# 7segement4digits1badidea-max7219-smd-mk-.net
KiCad netlist of a schematic drawn in EAGLE
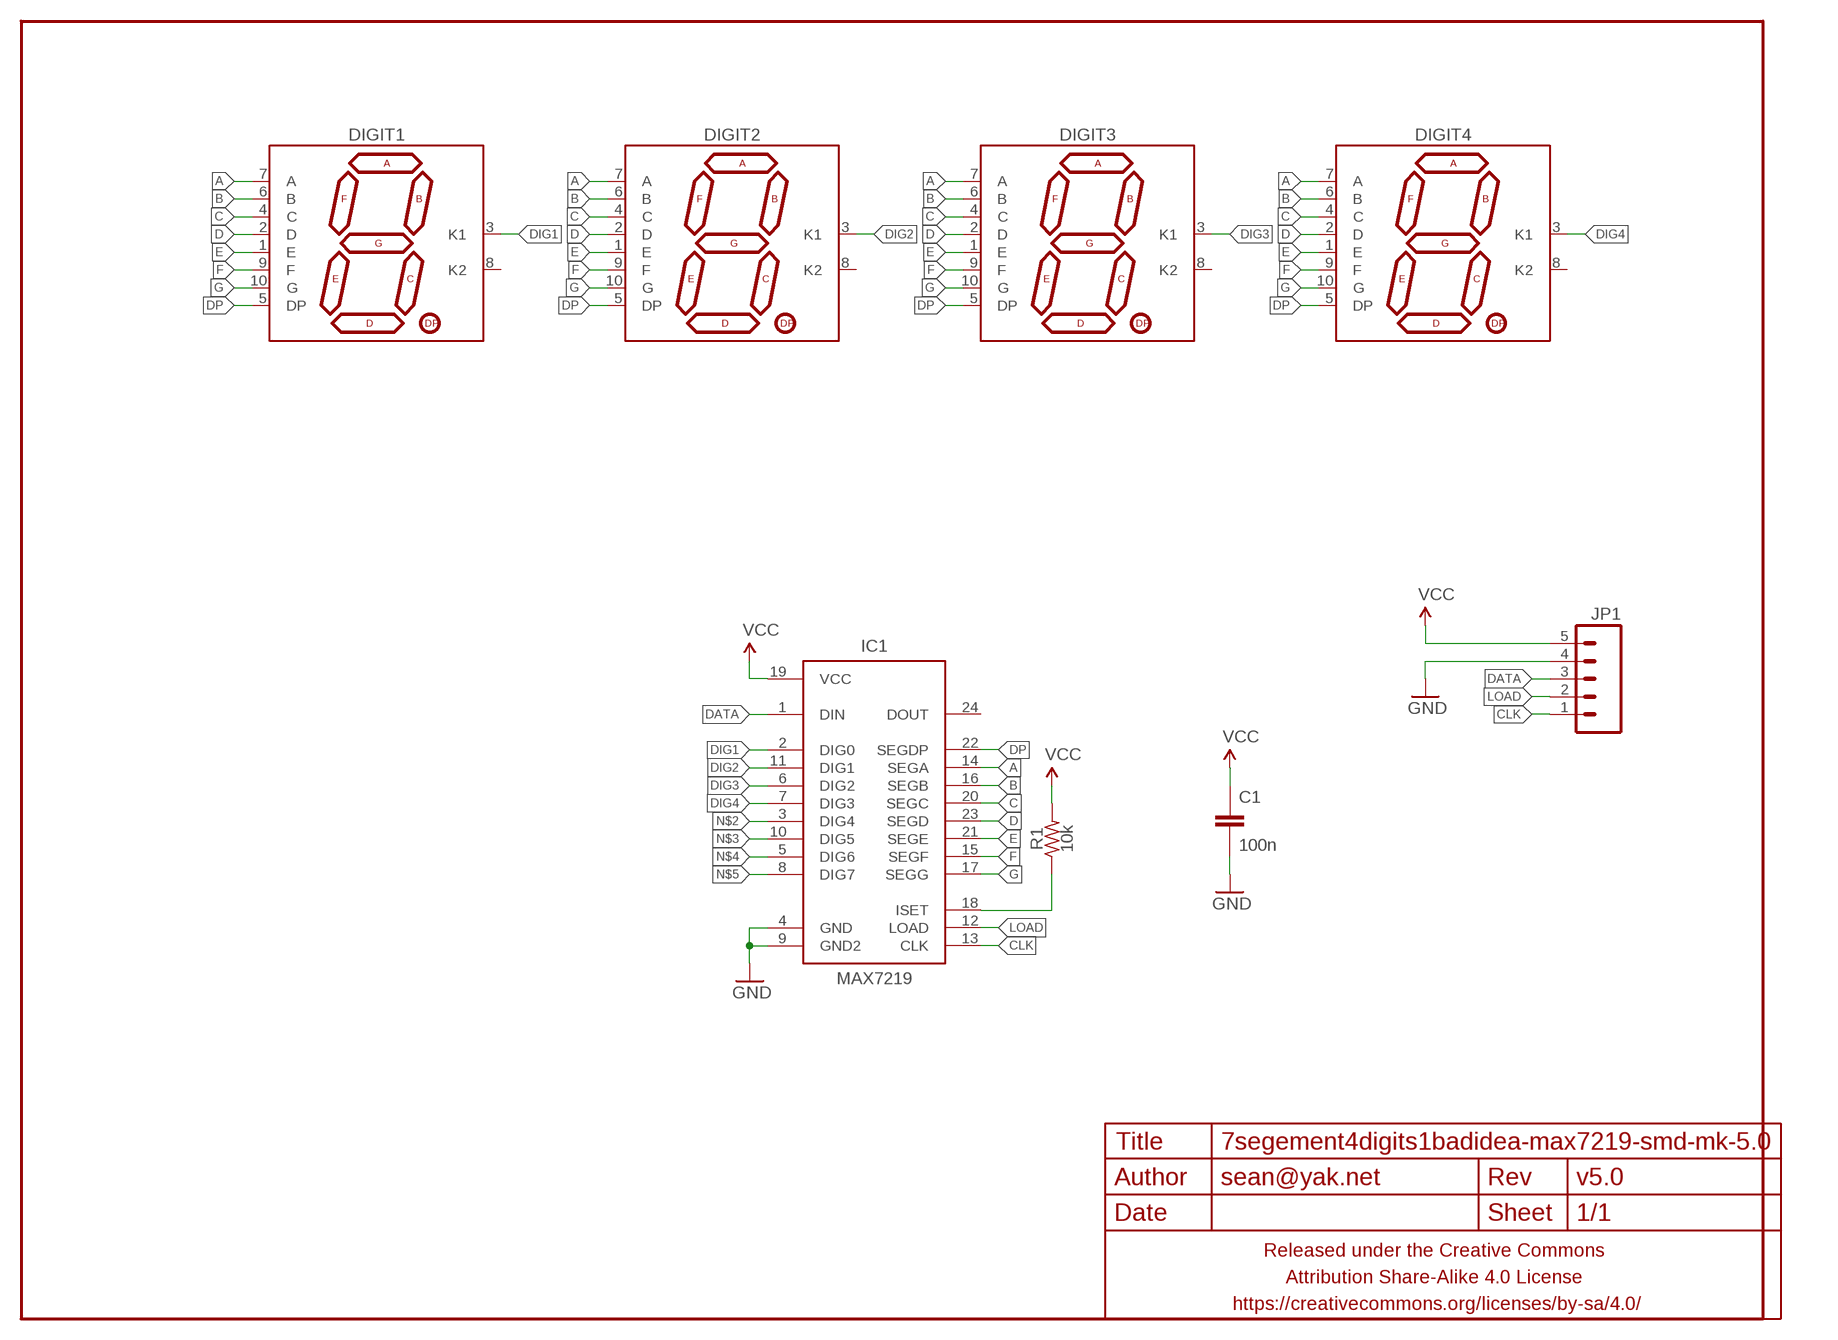
[diagram p0: schematic, sheet 1]

(export (version "E")
  (design (tool "Eeschema 10.0.6"))
  (components
    (comp (ref "C1")
      (value "100n")
      (footprint "eagle-import:C0805")
      (libsource (lib "eagle-import") (part "CAPACITOR-CERAMICC0805"))
    )
    (comp (ref "DIGIT1")
      (value "7SEG_1DIGPTH-25.4MM")
      (footprint "eagle-import:7SEG_1DIG_25.4MM")
      (libsource (lib "eagle-import") (part "7SEG_1DIGPTH-25.4MM"))
    )
    (comp (ref "DIGIT2")
      (value "7SEG_1DIGPTH-25.4MM")
      (footprint "eagle-import:7SEG_1DIG_25.4MM")
      (libsource (lib "eagle-import") (part "7SEG_1DIGPTH-25.4MM"))
    )
    (comp (ref "DIGIT3")
      (value "7SEG_1DIGPTH-25.4MM")
      (footprint "eagle-import:7SEG_1DIG_25.4MM")
      (libsource (lib "eagle-import") (part "7SEG_1DIGPTH-25.4MM"))
    )
    (comp (ref "DIGIT4")
      (value "7SEG_1DIGPTH-25.4MM")
      (footprint "eagle-import:7SEG_1DIG_25.4MM")
      (libsource (lib "eagle-import") (part "7SEG_1DIGPTH-25.4MM"))
    )
    (comp (ref "FRAME1")
      (value "FRAME-LETTERNO_PACKAGE")
      (footprint "eagle-import:DUMMY")
      (fields (field (name "DESIGNER") "sean@yak.net") (field (name "VERSION") "v5.0"))
      (libsource (lib "eagle-import") (part "FRAME-LETTERNO_PACKAGE"))
    )
    (comp (ref "IC1")
      (value "MAX7219")
      (footprint "eagle-import:SO24W")
      (libsource (lib "eagle-import") (part "MAX7219SOIC-W"))
    )
    (comp (ref "JP1")
      (value "M05PTH-CENTERED")
      (footprint "eagle-import:1X05_PTH_CENTERED")
      (libsource (lib "eagle-import") (part "M05PTH-CENTERED"))
    )
    (comp (ref "R1")
      (value "10k")
      (footprint "eagle-import:R0805")
      (libsource (lib "eagle-import") (part "RESISTORR0805"))
    )
  )
  (nets
    (net (code "1") (name "A") (class "Default")
      (node (ref "DIGIT1") (pin "7") (pinfunction "A_7") (pintype "bidirectional"))
      (node (ref "DIGIT2") (pin "7") (pinfunction "A_7") (pintype "bidirectional"))
      (node (ref "DIGIT3") (pin "7") (pinfunction "A_7") (pintype "bidirectional"))
      (node (ref "DIGIT4") (pin "7") (pinfunction "A_7") (pintype "bidirectional"))
      (node (ref "IC1") (pin "14") (pinfunction "SEGA_14") (pintype "bidirectional"))
    )
    (net (code "2") (name "B") (class "Default")
      (node (ref "DIGIT1") (pin "6") (pinfunction "B_6") (pintype "bidirectional"))
      (node (ref "DIGIT2") (pin "6") (pinfunction "B_6") (pintype "bidirectional"))
      (node (ref "DIGIT3") (pin "6") (pinfunction "B_6") (pintype "bidirectional"))
      (node (ref "DIGIT4") (pin "6") (pinfunction "B_6") (pintype "bidirectional"))
      (node (ref "IC1") (pin "16") (pinfunction "SEGB_16") (pintype "bidirectional"))
    )
    (net (code "3") (name "C") (class "Default")
      (node (ref "DIGIT1") (pin "4") (pinfunction "C_4") (pintype "bidirectional"))
      (node (ref "DIGIT2") (pin "4") (pinfunction "C_4") (pintype "bidirectional"))
      (node (ref "DIGIT3") (pin "4") (pinfunction "C_4") (pintype "bidirectional"))
      (node (ref "DIGIT4") (pin "4") (pinfunction "C_4") (pintype "bidirectional"))
      (node (ref "IC1") (pin "20") (pinfunction "SEGC_20") (pintype "bidirectional"))
    )
    (net (code "4") (name "CLK") (class "Default")
      (node (ref "IC1") (pin "13") (pinfunction "CLK_13") (pintype "bidirectional"))
      (node (ref "JP1") (pin "1") (pinfunction "1_1") (pintype "passive"))
    )
    (net (code "5") (name "D") (class "Default")
      (node (ref "DIGIT1") (pin "2") (pinfunction "D_2") (pintype "bidirectional"))
      (node (ref "DIGIT2") (pin "2") (pinfunction "D_2") (pintype "bidirectional"))
      (node (ref "DIGIT3") (pin "2") (pinfunction "D_2") (pintype "bidirectional"))
      (node (ref "DIGIT4") (pin "2") (pinfunction "D_2") (pintype "bidirectional"))
      (node (ref "IC1") (pin "23") (pinfunction "SEGD_23") (pintype "bidirectional"))
    )
    (net (code "6") (name "DATA") (class "Default")
      (node (ref "IC1") (pin "1") (pinfunction "DIN_1") (pintype "bidirectional"))
      (node (ref "JP1") (pin "3") (pinfunction "3_3") (pintype "passive"))
    )
    (net (code "7") (name "DIG1") (class "Default")
      (node (ref "DIGIT1") (pin "3") (pinfunction "K1_3") (pintype "bidirectional"))
      (node (ref "IC1") (pin "2") (pinfunction "DIG0_2") (pintype "bidirectional"))
    )
    (net (code "8") (name "DIG2") (class "Default")
      (node (ref "DIGIT2") (pin "3") (pinfunction "K1_3") (pintype "bidirectional"))
      (node (ref "IC1") (pin "11") (pinfunction "DIG1_11") (pintype "bidirectional"))
    )
    (net (code "9") (name "DIG3") (class "Default")
      (node (ref "DIGIT3") (pin "3") (pinfunction "K1_3") (pintype "bidirectional"))
      (node (ref "IC1") (pin "6") (pinfunction "DIG2_6") (pintype "bidirectional"))
    )
    (net (code "10") (name "DIG4") (class "Default")
      (node (ref "DIGIT4") (pin "3") (pinfunction "K1_3") (pintype "bidirectional"))
      (node (ref "IC1") (pin "7") (pinfunction "DIG3_7") (pintype "bidirectional"))
    )
    (net (code "11") (name "DP") (class "Default")
      (node (ref "DIGIT1") (pin "5") (pinfunction "DP_5") (pintype "bidirectional"))
      (node (ref "DIGIT2") (pin "5") (pinfunction "DP_5") (pintype "bidirectional"))
      (node (ref "DIGIT3") (pin "5") (pinfunction "DP_5") (pintype "bidirectional"))
      (node (ref "DIGIT4") (pin "5") (pinfunction "DP_5") (pintype "bidirectional"))
      (node (ref "IC1") (pin "22") (pinfunction "SEGDP_22") (pintype "bidirectional"))
    )
    (net (code "12") (name "E") (class "Default")
      (node (ref "DIGIT1") (pin "1") (pinfunction "E_1") (pintype "bidirectional"))
      (node (ref "DIGIT2") (pin "1") (pinfunction "E_1") (pintype "bidirectional"))
      (node (ref "DIGIT3") (pin "1") (pinfunction "E_1") (pintype "bidirectional"))
      (node (ref "DIGIT4") (pin "1") (pinfunction "E_1") (pintype "bidirectional"))
      (node (ref "IC1") (pin "21") (pinfunction "SEGE_21") (pintype "bidirectional"))
    )
    (net (code "13") (name "F") (class "Default")
      (node (ref "DIGIT1") (pin "9") (pinfunction "F_9") (pintype "bidirectional"))
      (node (ref "DIGIT2") (pin "9") (pinfunction "F_9") (pintype "bidirectional"))
      (node (ref "DIGIT3") (pin "9") (pinfunction "F_9") (pintype "bidirectional"))
      (node (ref "DIGIT4") (pin "9") (pinfunction "F_9") (pintype "bidirectional"))
      (node (ref "IC1") (pin "15") (pinfunction "SEGF_15") (pintype "bidirectional"))
    )
    (net (code "14") (name "G") (class "Default")
      (node (ref "DIGIT1") (pin "10") (pinfunction "G_10") (pintype "bidirectional"))
      (node (ref "DIGIT2") (pin "10") (pinfunction "G_10") (pintype "bidirectional"))
      (node (ref "DIGIT3") (pin "10") (pinfunction "G_10") (pintype "bidirectional"))
      (node (ref "DIGIT4") (pin "10") (pinfunction "G_10") (pintype "bidirectional"))
      (node (ref "IC1") (pin "17") (pinfunction "SEGG_17") (pintype "bidirectional"))
    )
    (net (code "15") (name "GND") (class "Default")
      (node (ref "C1") (pin "2") (pinfunction "2_2") (pintype "passive"))
      (node (ref "IC1") (pin "4") (pinfunction "GND_4") (pintype "bidirectional"))
      (node (ref "IC1") (pin "9") (pinfunction "GND2_9") (pintype "bidirectional"))
      (node (ref "JP1") (pin "4") (pinfunction "4_4") (pintype "passive"))
    )
    (net (code "16") (name "LOAD") (class "Default")
      (node (ref "IC1") (pin "12") (pinfunction "LOAD_12") (pintype "bidirectional"))
      (node (ref "JP1") (pin "2") (pinfunction "2_2") (pintype "passive"))
    )
    (net (code "17") (name "N$2") (class "Default")
      (node (ref "IC1") (pin "3") (pinfunction "DIG4_3") (pintype "bidirectional"))
    )
    (net (code "18") (name "N$3") (class "Default")
      (node (ref "IC1") (pin "10") (pinfunction "DIG5_10") (pintype "bidirectional"))
    )
    (net (code "19") (name "N$4") (class "Default")
      (node (ref "IC1") (pin "5") (pinfunction "DIG6_5") (pintype "bidirectional"))
    )
    (net (code "20") (name "N$5") (class "Default")
      (node (ref "IC1") (pin "8") (pinfunction "DIG7_8") (pintype "bidirectional"))
    )
    (net (code "21") (name "Net-(IC1-ISET)") (class "Default")
      (node (ref "IC1") (pin "18") (pinfunction "ISET_18") (pintype "bidirectional"))
      (node (ref "R1") (pin "1") (pinfunction "1_1") (pintype "passive"))
    )
    (net (code "22") (name "VCC") (class "Default")
      (node (ref "C1") (pin "1") (pinfunction "1_1") (pintype "passive"))
      (node (ref "IC1") (pin "19") (pinfunction "VCC_19") (pintype "bidirectional"))
      (node (ref "JP1") (pin "5") (pinfunction "5_5") (pintype "passive"))
      (node (ref "R1") (pin "2") (pinfunction "2_2") (pintype "passive"))
    )
    (net (code "23") (name "unconnected-(DIGIT1-K2-Pad8)") (class "Default")
      (node (ref "DIGIT1") (pin "8") (pinfunction "K2_8") (pintype "bidirectional"))
    )
    (net (code "24") (name "unconnected-(DIGIT2-K2-Pad8)") (class "Default")
      (node (ref "DIGIT2") (pin "8") (pinfunction "K2_8") (pintype "bidirectional"))
    )
    (net (code "25") (name "unconnected-(DIGIT3-K2-Pad8)") (class "Default")
      (node (ref "DIGIT3") (pin "8") (pinfunction "K2_8") (pintype "bidirectional"))
    )
    (net (code "26") (name "unconnected-(DIGIT4-K2-Pad8)") (class "Default")
      (node (ref "DIGIT4") (pin "8") (pinfunction "K2_8") (pintype "bidirectional"))
    )
    (net (code "27") (name "unconnected-(IC1-DOUT-Pad24)") (class "Default")
      (node (ref "IC1") (pin "24") (pinfunction "DOUT_24") (pintype "bidirectional"))
    )
  )
)
